# hal9kpost.net
KiCad netlist of a schematic drawn in EAGLE
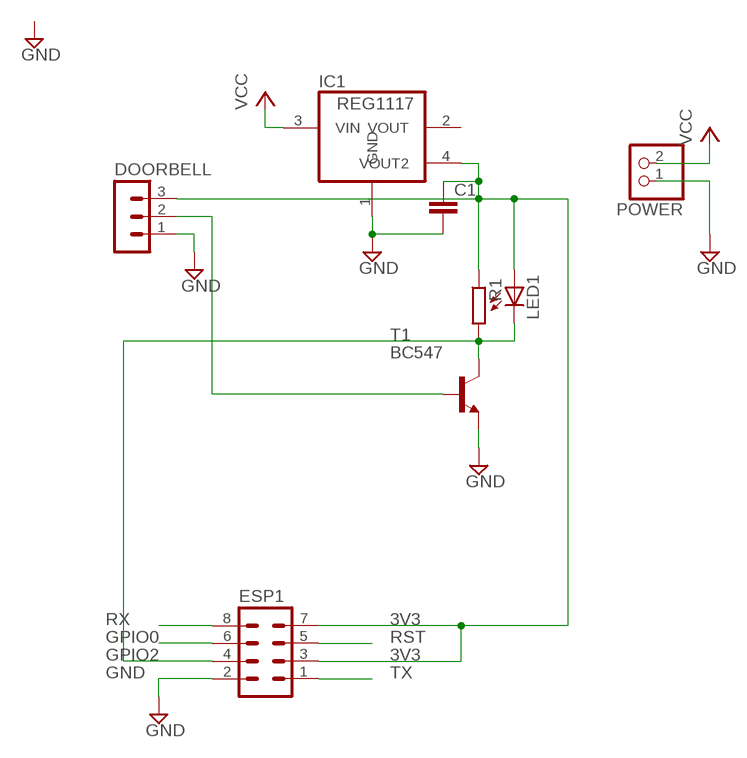
[diagram p0: schematic, sheet 1]

(export (version "E")
  (design (tool "Eeschema 10.0.6"))
  (components
    (comp (ref "C1")
      (value "C-EUC0805K")
      (footprint "eagle-import:C0805K")
      (libsource (lib "eagle-import") (part "C-EUC0805K"))
    )
    (comp (ref "DOORBELL")
      (value "MA03-1")
      (footprint "eagle-import:MA03-1")
      (libsource (lib "eagle-import") (part "MA03-1"))
    )
    (comp (ref "ESP1")
      (value "MA04-2")
      (footprint "eagle-import:MA04-2")
      (libsource (lib "eagle-import") (part "MA04-2"))
    )
    (comp (ref "IC1")
      (value "REG1117")
      (footprint "eagle-import:SOT223")
      (libsource (lib "eagle-import") (part "REG1117"))
    )
    (comp (ref "LED1")
      (value "LED5MM")
      (footprint "eagle-import:LED5MM")
      (libsource (lib "eagle-import") (part "LED5MM"))
    )
    (comp (ref "POWER")
      (value "PINHD-1X2")
      (footprint "eagle-import:1X02")
      (libsource (lib "eagle-import") (part "PINHD-1X2"))
    )
    (comp (ref "R1")
      (value "R-EU_0207/10")
      (footprint "eagle-import:0207_10")
      (libsource (lib "eagle-import") (part "R-EU_0207/10"))
    )
    (comp (ref "T1")
      (value "BC547")
      (footprint "eagle-import:TO92")
      (libsource (lib "eagle-import") (part "BC547"))
    )
  )
  (nets
    (net (code "1") (name "/3V3") (class "Default")
      (node (ref "C1") (pin "1") (pinfunction "1_1") (pintype "passive"))
      (node (ref "DOORBELL") (pin "3") (pinfunction "3_3") (pintype "passive"))
      (node (ref "ESP1") (pin "3") (pinfunction "3_3") (pintype "passive"))
      (node (ref "ESP1") (pin "7") (pinfunction "7_7") (pintype "passive"))
      (node (ref "IC1") (pin "4") (pinfunction "VOUT2_4") (pintype "bidirectional"))
      (node (ref "LED1") (pin "A") (pinfunction "A_A") (pintype "passive"))
      (node (ref "R1") (pin "1") (pinfunction "1_1") (pintype "passive"))
    )
    (net (code "2") (name "/GPIO0") (class "Default")
      (node (ref "ESP1") (pin "6") (pinfunction "6_6") (pintype "passive"))
    )
    (net (code "3") (name "/GPIO2") (class "Default")
      (node (ref "ESP1") (pin "4") (pinfunction "4_4") (pintype "passive"))
      (node (ref "LED1") (pin "K") (pinfunction "C_K") (pintype "passive"))
      (node (ref "R1") (pin "2") (pinfunction "2_2") (pintype "passive"))
      (node (ref "T1") (pin "3") (pinfunction "C_3") (pintype "passive"))
    )
    (net (code "4") (name "/RST") (class "Default")
      (node (ref "ESP1") (pin "5") (pinfunction "5_5") (pintype "passive"))
    )
    (net (code "5") (name "/RX") (class "Default")
      (node (ref "ESP1") (pin "8") (pinfunction "8_8") (pintype "passive"))
    )
    (net (code "6") (name "/TX") (class "Default")
      (node (ref "ESP1") (pin "1") (pinfunction "1_1") (pintype "passive"))
    )
    (net (code "7") (name "GND") (class "Default")
      (node (ref "C1") (pin "2") (pinfunction "2_2") (pintype "passive"))
      (node (ref "DOORBELL") (pin "1") (pinfunction "1_1") (pintype "passive"))
      (node (ref "ESP1") (pin "2") (pinfunction "2_2") (pintype "passive"))
      (node (ref "IC1") (pin "1") (pinfunction "GND_1") (pintype "power_in"))
      (node (ref "POWER") (pin "1") (pinfunction "1_1") (pintype "passive"))
      (node (ref "T1") (pin "1") (pinfunction "E_1") (pintype "passive"))
    )
    (net (code "8") (name "Net-(T1-B)") (class "Default")
      (node (ref "DOORBELL") (pin "2") (pinfunction "2_2") (pintype "passive"))
      (node (ref "T1") (pin "2") (pinfunction "B_2") (pintype "passive"))
    )
    (net (code "9") (name "VCC") (class "Default")
      (node (ref "IC1") (pin "3") (pinfunction "VIN_3") (pintype "input"))
      (node (ref "POWER") (pin "2") (pinfunction "2_2") (pintype "passive"))
    )
    (net (code "10") (name "unconnected-(IC1-VOUT-Pad2)") (class "Default")
      (node (ref "IC1") (pin "2") (pinfunction "VOUT_2") (pintype "output"))
    )
  )
)
